# LCDTFTAVDD_TPS61040.net
KiCad netlist of a schematic drawn in Altium Designer
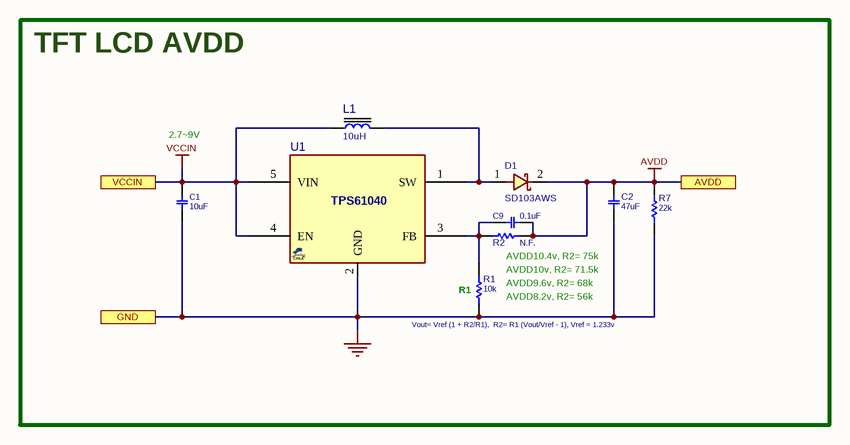
[diagram p0: LCDTFTAVDD_TPS61040.SchDoc]

(export (version "E")
  (design (tool "Eeschema 10.0.6"))
  (components
    (comp (ref "C1")
      (value "10uF")
      (footprint "C0402")
      (description "CAP, MLCC")
      (fields (field (name "MANF_P#") "CL10A106MO8NQNC") (field (name "MANF") "Samsung"))
      (libsource (lib "passive_smd") (part "CAP_SMD_MLCC"))
    )
    (comp (ref "C2")
      (value "47uF")
      (footprint "C1206")
      (description "CAP, MLCC")
      (fields (field (name "MANF_P#") "GRM31CR61E476ME44L") (field (name "MANF") "Murata"))
      (libsource (lib "passive_smd") (part "CAP_SMD_MLCC"))
    )
    (comp (ref "C9")
      (value "0.1uF")
      (footprint "C0402")
      (description "CAP, MLCC, 100nF, 50V, X7R, 10%, 0402C")
      (fields (field (name "MANF") "Murata") (field (name "MANF_P#") "GCM155R71H104KE02D"))
      (libsource (lib "passive_mlcc_smd") (part "CAP_SMD_MLCC_100n50V"))
    )
    (comp (ref "D1")
      (value "SD103AWS")
      (footprint "D_SOD323")
      (description "DIODE, SCHOTTKY, 40V, 2A")
      (fields (field (name "MANF") "DIODES"))
      (libsource (lib "diode") (part "DIODE_SMD_SCHOTTKY_1N5819"))
    )
    (comp (ref "L1")
      (value "10uH")
      (footprint "L_4")
      (description "INDUCTOR, POWER, SMD")
      (fields (field (name "MANF_P#") "GCD43-100MC"))
      (libsource (lib "passive") (part "INDPWR_SMD"))
    )
    (comp (ref "R1")
      (value "10k")
      (footprint "R0402")
      (description "RESISTOR, SMD, 20K, 0402")
      (fields (field (name "MANF") "Yageo") (field (name "MANF_P#") "RK73H1ETTP2002F"))
      (libsource (lib "chila_passive") (part "RES_SMD"))
    )
    (comp (ref "R2")
      (value "N.F.")
      (footprint "R0402")
      (description "RESISTOR, SMD, 20K, 0402")
      (fields (field (name "MANF") "Yageo") (field (name "MANF_P#") "RK73H1ETTP2002F"))
      (libsource (lib "chila_passive") (part "RES_SMD"))
    )
    (comp (ref "R7")
      (value "22k")
      (footprint "R0402")
      (description "RESISTOR, SMD, 20K, 0402")
      (fields (field (name "MANF") "Yageo") (field (name "MANF_P#") "RK73H1ETTP2002F"))
      (libsource (lib "chila_passive") (part "RES_SMD"))
    )
    (comp (ref "U1")
      (value "TPS61040")
      (footprint "SOT23_5")
      (description "REG, Switching, Boost, 0.4A, ADJ, 1MHz, SOT-23-5")
      (fields (field (name "MANF_P#") "TPS61040DBVR") (field (name "MANF") "TI"))
      (libsource (lib "pwr_switching_boost") (part "VREG_TPS61040_SOT23"))
    )
  )
  (nets
    (net (code "1") (name "AVDD") (class "Default")
      (node (ref "C2") (pin "2") (pinfunction "2_2") (pintype "passive"))
      (node (ref "C9") (pin "1") (pinfunction "1_1") (pintype "passive"))
      (node (ref "D1") (pin "2") (pinfunction "2_2") (pintype "passive"))
      (node (ref "R2") (pin "2") (pinfunction "2_2") (pintype "passive"))
      (node (ref "R7") (pin "1") (pinfunction "1_1") (pintype "passive"))
    )
    (net (code "2") (name "GND") (class "Default")
      (node (ref "C1") (pin "1") (pinfunction "1_1") (pintype "passive"))
      (node (ref "C2") (pin "1") (pinfunction "1_1") (pintype "passive"))
      (node (ref "R1") (pin "2") (pinfunction "2_2") (pintype "passive"))
      (node (ref "R7") (pin "2") (pinfunction "2_2") (pintype "passive"))
      (node (ref "U1") (pin "2") (pinfunction "GND_2") (pintype "tri_state"))
    )
    (net (code "3") (name "Net-(U1-FB)") (class "Default")
      (node (ref "C9") (pin "2") (pinfunction "2_2") (pintype "passive"))
      (node (ref "R1") (pin "1") (pinfunction "1_1") (pintype "passive"))
      (node (ref "R2") (pin "1") (pinfunction "1_1") (pintype "passive"))
      (node (ref "U1") (pin "3") (pinfunction "FB_3") (pintype "tri_state"))
    )
    (net (code "4") (name "Net-(U1-SW)") (class "Default")
      (node (ref "D1") (pin "1") (pinfunction "1_1") (pintype "passive"))
      (node (ref "L1") (pin "2") (pinfunction "2_2") (pintype "passive"))
      (node (ref "U1") (pin "1") (pinfunction "SW_1") (pintype "tri_state"))
    )
    (net (code "5") (name "VCCIN") (class "Default")
      (node (ref "C1") (pin "2") (pinfunction "2_2") (pintype "passive"))
      (node (ref "L1") (pin "1") (pinfunction "1_1") (pintype "passive"))
      (node (ref "U1") (pin "4") (pinfunction "EN_4") (pintype "tri_state"))
      (node (ref "U1") (pin "5") (pinfunction "VIN_5") (pintype "tri_state"))
    )
  )
)
